# Battery.net
KiCad netlist of a schematic drawn in Altium Designer
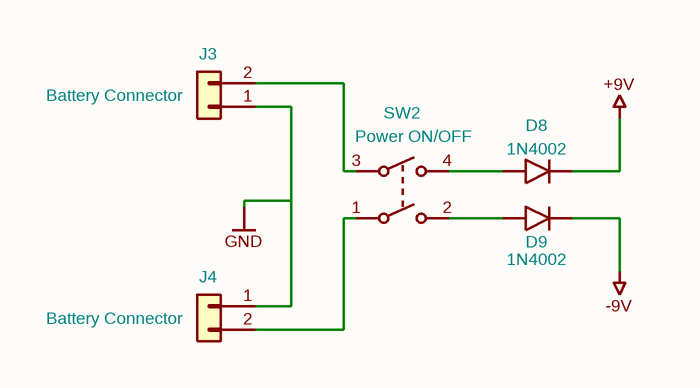
[diagram p0: Battery.SchDoc]

(export (version "E")
  (design (tool "Eeschema 10.0.6"))
  (components
    (comp (ref "D8") (value "1N4002") (libsource (lib "Diode") (part "1N4002")))
    (comp (ref "D9") (value "1N4002") (libsource (lib "Diode") (part "1N4002")))
    (comp (ref "J3") (value "Battery Connector") (libsource (lib "*") (part "Conn_01x02_1")))
    (comp (ref "J4") (value "Battery Connector") (libsource (lib "Connector_Generic") (part "Conn_01x02")))
    (comp (ref "SW2") (value "Power ON/OFF") (libsource (lib "Switch") (part "SW_DPST")))
  )
  (nets
    (net (code "1") (name "+9V") (class "Default")
      (node (ref "D8") (pin "1") (pinfunction "K_1") (pintype "passive"))
    )
    (net (code "2") (name "-9V") (class "Default")
      (node (ref "D9") (pin "1") (pinfunction "K_1") (pintype "passive"))
    )
    (net (code "3") (name "GND") (class "Default")
      (node (ref "J3") (pin "1") (pinfunction "Pin_1_1") (pintype "passive"))
      (node (ref "J4") (pin "1") (pinfunction "Pin_1_1") (pintype "passive"))
    )
    (net (code "4") (name "Net-(D8-A)") (class "Default")
      (node (ref "D8") (pin "2") (pinfunction "A_2") (pintype "passive"))
      (node (ref "SW2") (pin "4") (pinfunction "4_4") (pintype "passive"))
    )
    (net (code "5") (name "Net-(D9-A)") (class "Default")
      (node (ref "D9") (pin "2") (pinfunction "A_2") (pintype "passive"))
      (node (ref "SW2") (pin "2") (pinfunction "2_2") (pintype "passive"))
    )
    (net (code "6") (name "Net-(J3-Pin_2)") (class "Default")
      (node (ref "J3") (pin "2") (pinfunction "Pin_2_2") (pintype "passive"))
      (node (ref "SW2") (pin "3") (pinfunction "3_3") (pintype "passive"))
    )
    (net (code "7") (name "Net-(J4-Pad2)") (class "Default")
      (node (ref "J4") (pin "2") (pinfunction "2_2") (pintype "passive"))
      (node (ref "SW2") (pin "1") (pinfunction "1_1") (pintype "passive"))
    )
  )
)
